# MPPT.net
KiCad netlist of a schematic drawn in Altium Designer
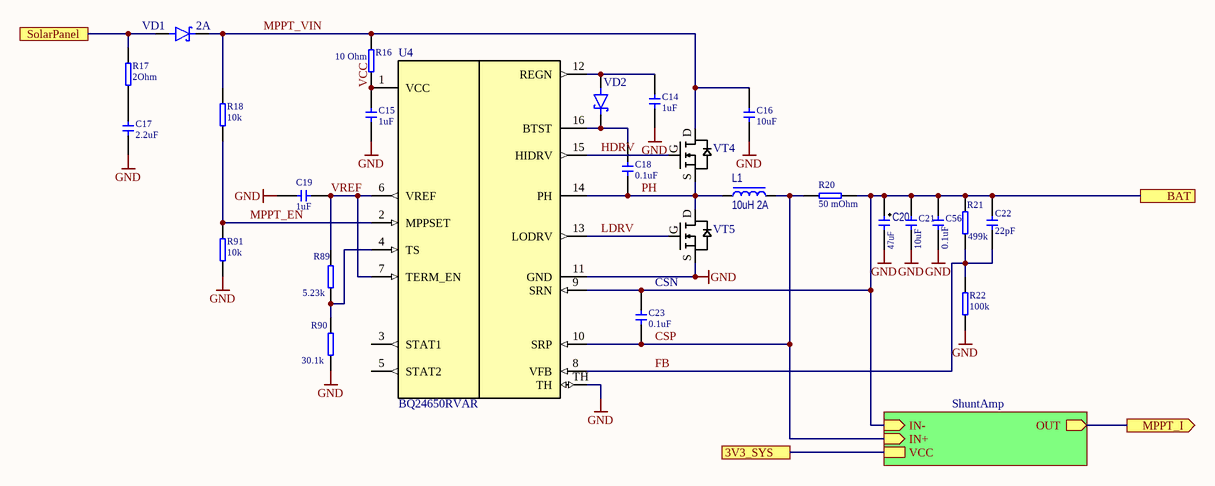
[diagram p0: MPPT.SchDoc]

(export (version "E")
  (design (tool "Eeschema 10.0.6"))
  (components
    (comp (ref "C14")
      (value "1uF")
      (footprint "CERCAP 0402")
      (description "Capacitor")
      (fields (field (name "VOLTAGE") "50V") (field (name "Comment") "CERCAP 0402 1uF 50V X7R"))
      (libsource (lib "!main") (part "!Capacitor"))
    )
    (comp (ref "C15")
      (value "1uF")
      (footprint "CERCAP 0402")
      (description "Capacitor")
      (fields (field (name "VOLTAGE") "50V") (field (name "Comment") "CERCAP 0402 1uF 50V X7R"))
      (libsource (lib "!main") (part "!Capacitor"))
    )
    (comp (ref "C16")
      (value "10uF")
      (footprint "CERCAP 0603")
      (description "Capacitor")
      (fields (field (name "VOLTAGE") "50V") (field (name "Comment") "CERCAP 0603 10uF 50V X7R"))
      (libsource (lib "!main") (part "!Capacitor"))
    )
    (comp (ref "C17")
      (value "2.2uF")
      (footprint "CERCAP 0603")
      (description "Capacitor")
      (fields (field (name "VOLTAGE") "50V") (field (name "Comment") "CERCAP 0603 2.2uF 50V X7R"))
      (libsource (lib "!main") (part "!Capacitor"))
    )
    (comp (ref "C18")
      (value "0.1uF")
      (footprint "CERCAP 0402")
      (description "Capacitor")
      (fields (field (name "VOLTAGE") "50V") (field (name "Comment") "CERCAP 0402 0.1uF 50V X7R"))
      (libsource (lib "!main") (part "!Capacitor"))
    )
    (comp (ref "C19")
      (value "1uF")
      (footprint "CERCAP 0402")
      (description "Capacitor")
      (fields (field (name "VOLTAGE") "50V") (field (name "Comment") "CERCAP 0402 1uF 50V X7R"))
      (libsource (lib "!main") (part "!Capacitor"))
    )
    (comp (ref "C20")
      (value "47uF")
      (footprint "TECAP B")
      (description "Capacitor Polar")
      (fields (field (name "Comment") "TAJC686K016RNJ"))
      (libsource (lib "!main") (part "CapacitorP"))
    )
    (comp (ref "C21")
      (value "10uF")
      (footprint "CERCAP 0603")
      (description "Capacitor")
      (fields (field (name "VOLTAGE") "50V") (field (name "Comment") "CERCAP 0603 10uF 50V X7R"))
      (libsource (lib "!main") (part "!Capacitor"))
    )
    (comp (ref "C22")
      (value "22pF")
      (footprint "CERCAP 0402")
      (description "Capacitor")
      (fields (field (name "VOLTAGE") "50V") (field (name "Comment") "CERCAP 0402 22pF 50V X7R"))
      (libsource (lib "!main") (part "!Capacitor"))
    )
    (comp (ref "C23")
      (value "0.1uF")
      (footprint "CERCAP 0402")
      (description "Capacitor")
      (fields (field (name "VOLTAGE") "50V") (field (name "Comment") "CERCAP 0402 0.1uF 50V X7R"))
      (libsource (lib "!main") (part "!Capacitor"))
    )
    (comp (ref "C56")
      (value "0.1uF")
      (footprint "CERCAP 0402")
      (description "Capacitor")
      (fields (field (name "VOLTAGE") "50V") (field (name "Comment") "CERCAP 0402 0.1uF 50V X7R"))
      (libsource (lib "!main") (part "!Capacitor"))
    )
    (comp (ref "L1")
      (value "10uH 2A")
      (footprint "IND-4.6x4.6")
      (description "Inductor")
      (fields (field (name "Comment") "IND-4.6x4.6 10uH 2A"))
      (libsource (lib "!main") (part "Inductor"))
    )
    (comp (ref "R16")
      (value "10 Ohm")
      (footprint "RES 0402")
      (description "Resistor")
      (fields (field (name "Comment") "RES 0402 10 Ohm"))
      (libsource (lib "!main") (part "!Resistor"))
    )
    (comp (ref "R17")
      (value "2Ohm")
      (footprint "RES 0402")
      (description "Resistor")
      (fields (field (name "Comment") "RES 0402 2Ohm"))
      (libsource (lib "!main") (part "!Resistor"))
    )
    (comp (ref "R18")
      (value "10k")
      (footprint "RES 0402")
      (description "Resistor")
      (fields (field (name "Comment") "RES 0402 10k"))
      (libsource (lib "!main") (part "!Resistor"))
    )
    (comp (ref "R20")
      (value "50 mOhm")
      (footprint "RES 1210")
      (description "Resistor")
      (fields (field (name "Comment") "RES 1210 50 mOhm"))
      (libsource (lib "!main") (part "!Resistor"))
    )
    (comp (ref "R21")
      (value "499k")
      (footprint "RES 0402")
      (description "Resistor")
      (fields (field (name "Comment") "RES 0402 499k"))
      (libsource (lib "!main") (part "!Resistor"))
    )
    (comp (ref "R22")
      (value "100k")
      (footprint "RES 0402")
      (description "Resistor")
      (fields (field (name "Comment") "RES 0402 100k"))
      (libsource (lib "!main") (part "!Resistor"))
    )
    (comp (ref "R89")
      (value "5.23k")
      (footprint "RES 0402")
      (description "Resistor")
      (fields (field (name "Comment") "RES 0402 5.23k"))
      (libsource (lib "!main") (part "!Resistor"))
    )
    (comp (ref "R90")
      (value "30.1k")
      (footprint "RES 0402")
      (description "Resistor")
      (fields (field (name "Comment") "RES 0402 30.1k"))
      (libsource (lib "!main") (part "!Resistor"))
    )
    (comp (ref "R91")
      (value "10k")
      (footprint "RES 0402")
      (description "Resistor")
      (fields (field (name "Comment") "RES 0402 10k"))
      (libsource (lib "!main") (part "!Resistor"))
    )
    (comp (ref "U4")
      (value "BQ24650RVAR")
      (footprint "QFN-16(3,5x3,5)")
      (description "MPPT charger")
      (libsource (lib "dc-dc") (part "BQ24650RVAR"))
    )
    (comp (ref "VD1")
      (value "Shottly diode SOD-123")
      (footprint "SOD-123")
      (description "Diode Shottky")
      (libsource (lib "diodes") (part "DiodeS"))
    )
    (comp (ref "VD2")
      (value "Shottly diode SOD-123")
      (footprint "SOD-123")
      (description "Diode Shottky")
      (libsource (lib "diodes") (part "DiodeS"))
    )
    (comp (ref "VT4")
      (value "NTMFS5C670NLT1G")
      (footprint "DFN-8_3x3")
      (description "generic N mosfet")
      (libsource (lib "transistors") (part "!Generic N MOSFET"))
    )
    (comp (ref "VT5")
      (value "NTMFS5C670NLT1G")
      (footprint "DFN-8_3x3")
      (description "generic N mosfet")
      (libsource (lib "transistors") (part "!Generic N MOSFET"))
    )
  )
  (nets
    (net (code "2") (name "/BAT") (class "Default")
      (node (ref "C20") (pin "1") (pinfunction "+_1") (pintype "passive"))
      (node (ref "C21") (pin "2") (pintype "passive"))
      (node (ref "C22") (pin "2") (pintype "passive"))
      (node (ref "C23") (pin "2") (pintype "passive"))
      (node (ref "C56") (pin "2") (pintype "passive"))
      (node (ref "R20") (pin "2") (pinfunction "12_2") (pintype "passive"))
      (node (ref "R21") (pin "2") (pinfunction "12_2") (pintype "passive"))
      (node (ref "U4") (pin "9") (pinfunction "SRN_9") (pintype "input"))
    )
    (net (code "3") (name "/CSP") (class "Default")
      (node (ref "C23") (pin "1") (pintype "passive"))
      (node (ref "L1") (pin "2") (pinfunction "8_2") (pintype "passive"))
      (node (ref "R20") (pin "1") (pinfunction "11_1") (pintype "passive"))
      (node (ref "U4") (pin "10") (pinfunction "SRP_10") (pintype "input"))
    )
    (net (code "4") (name "/FB") (class "Default")
      (node (ref "C22") (pin "1") (pintype "passive"))
      (node (ref "R21") (pin "1") (pinfunction "11_1") (pintype "passive"))
      (node (ref "R22") (pin "2") (pinfunction "12_2") (pintype "passive"))
      (node (ref "U4") (pin "8") (pinfunction "VFB_8") (pintype "input"))
    )
    (net (code "5") (name "/HDRV") (class "Default")
      (node (ref "U4") (pin "15") (pinfunction "HIDRV_15") (pintype "output"))
      (node (ref "VT4") (pin "G2") (pintype "passive"))
    )
    (net (code "6") (name "/LDRV") (class "Default")
      (node (ref "U4") (pin "13") (pinfunction "LODRV_13") (pintype "output"))
      (node (ref "VT5") (pin "G2") (pintype "passive"))
    )
    (net (code "7") (name "/MPPT_EN") (class "Default")
      (node (ref "R18") (pin "1") (pinfunction "11_1") (pintype "passive"))
      (node (ref "R91") (pin "2") (pinfunction "12_2") (pintype "passive"))
      (node (ref "U4") (pin "2") (pinfunction "MPPSET_2") (pintype "input"))
    )
    (net (code "9") (name "/MPPT_VIN") (class "Default")
      (node (ref "C16") (pin "1") (pintype "passive"))
      (node (ref "R16") (pin "2") (pinfunction "12_2") (pintype "passive"))
      (node (ref "R18") (pin "2") (pinfunction "12_2") (pintype "passive"))
      (node (ref "VD1") (pin "C") (pinfunction "Cathode_C") (pintype "passive"))
      (node (ref "VT4") (pin "D6") (pintype "passive"))
    )
    (net (code "10") (name "/PH") (class "Default")
      (node (ref "C18") (pin "1") (pintype "passive"))
      (node (ref "L1") (pin "1") (pinfunction "7_1") (pintype "passive"))
      (node (ref "U4") (pin "14") (pinfunction "PH_14") (pintype "power_in"))
      (node (ref "VT4") (pin "S1") (pintype "passive"))
      (node (ref "VT5") (pin "D6") (pintype "passive"))
    )
    (net (code "11") (name "/SolarPanel") (class "Default")
      (node (ref "R17") (pin "2") (pinfunction "12_2") (pintype "passive"))
      (node (ref "VD1") (pin "A") (pinfunction "Anode_A") (pintype "passive"))
    )
    (net (code "12") (name "/VCC") (class "Default")
      (node (ref "C15") (pin "2") (pintype "passive"))
      (node (ref "R16") (pin "1") (pinfunction "11_1") (pintype "passive"))
      (node (ref "U4") (pin "1") (pinfunction "VCC_1") (pintype "power_in"))
    )
    (net (code "13") (name "/VREF") (class "Default")
      (node (ref "C19") (pin "1") (pintype "passive"))
      (node (ref "R89") (pin "2") (pinfunction "12_2") (pintype "passive"))
      (node (ref "U4") (pin "6") (pinfunction "VREF_6") (pintype "output"))
      (node (ref "U4") (pin "7") (pinfunction "TERM_EN_7") (pintype "input"))
    )
    (net (code "14") (name "GND") (class "Default")
      (node (ref "C14") (pin "1") (pintype "passive"))
      (node (ref "C15") (pin "1") (pintype "passive"))
      (node (ref "C16") (pin "2") (pintype "passive"))
      (node (ref "C17") (pin "1") (pintype "passive"))
      (node (ref "C19") (pin "2") (pintype "passive"))
      (node (ref "C20") (pin "2") (pinfunction "-_2") (pintype "passive"))
      (node (ref "C21") (pin "1") (pintype "passive"))
      (node (ref "C56") (pin "1") (pintype "passive"))
      (node (ref "R22") (pin "1") (pinfunction "11_1") (pintype "passive"))
      (node (ref "R90") (pin "1") (pinfunction "11_1") (pintype "passive"))
      (node (ref "R91") (pin "1") (pinfunction "11_1") (pintype "passive"))
      (node (ref "U4") (pin "11") (pinfunction "GND_11") (pintype "power_in"))
      (node (ref "U4") (pin "TH") (pinfunction "TH_TH") (pintype "bidirectional"))
      (node (ref "VT5") (pin "S1") (pintype "passive"))
    )
    (net (code "15") (name "Net-(R17-11)") (class "Default")
      (node (ref "C17") (pin "2") (pintype "passive"))
      (node (ref "R17") (pin "1") (pinfunction "11_1") (pintype "passive"))
    )
    (net (code "16") (name "Net-(R89-11)") (class "Default")
      (node (ref "R89") (pin "1") (pinfunction "11_1") (pintype "passive"))
      (node (ref "R90") (pin "2") (pinfunction "12_2") (pintype "passive"))
      (node (ref "U4") (pin "4") (pinfunction "TS_4") (pintype "input"))
    )
    (net (code "17") (name "Net-(U4-BTST)") (class "Default")
      (node (ref "C18") (pin "2") (pintype "passive"))
      (node (ref "U4") (pin "16") (pinfunction "BTST_16") (pintype "power_in"))
      (node (ref "VD2") (pin "C") (pinfunction "Cathode_C") (pintype "passive"))
    )
    (net (code "18") (name "Net-(U4-REGN)") (class "Default")
      (node (ref "C14") (pin "2") (pintype "passive"))
      (node (ref "U4") (pin "12") (pinfunction "REGN_12") (pintype "output"))
      (node (ref "VD2") (pin "A") (pinfunction "Anode_A") (pintype "passive"))
    )
    (net (code "19") (name "unconnected-(U4-STAT1-Pad3)") (class "Default")
      (node (ref "U4") (pin "3") (pinfunction "STAT1_3") (pintype "output"))
    )
    (net (code "20") (name "unconnected-(U4-STAT2-Pad5)") (class "Default")
      (node (ref "U4") (pin "5") (pinfunction "STAT2_5") (pintype "output"))
    )
  )
)
